# Master.net
KiCad netlist of a schematic drawn in EAGLE
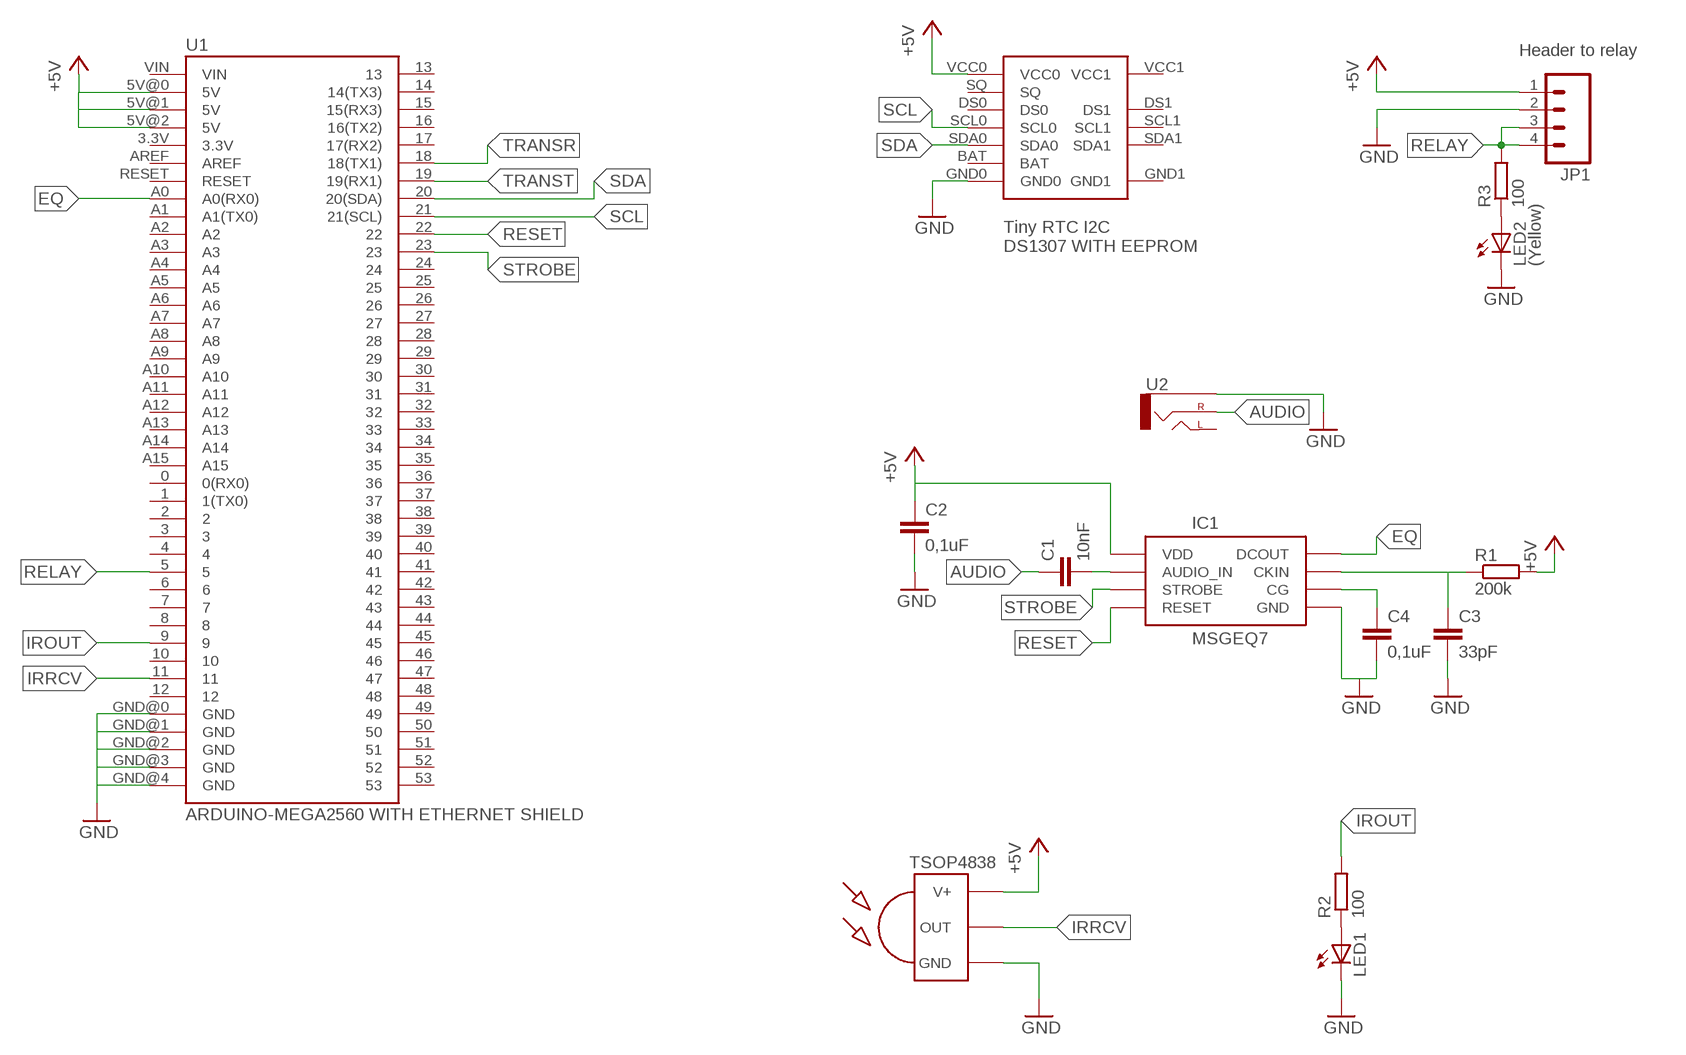
[diagram p0: schematic, sheet 1]

(export (version "E")
  (design (tool "Eeschema 10.0.6"))
  (components
    (comp (ref "C1")
      (value "10nF")
      (footprint "eagle-import:CAP-PTH-SMALLEZ")
      (libsource (lib "eagle-import") (part "CAPEZ"))
    )
    (comp (ref "C2")
      (value "0,1uF")
      (footprint "eagle-import:CAP-PTH-SMALLEZ")
      (libsource (lib "eagle-import") (part "CAPEZ"))
    )
    (comp (ref "C3")
      (value "33pF")
      (footprint "eagle-import:CAP-PTH-SMALLEZ")
      (libsource (lib "eagle-import") (part "CAPEZ"))
    )
    (comp (ref "C4")
      (value "0,1uF")
      (footprint "eagle-import:CAP-PTH-SMALLEZ")
      (libsource (lib "eagle-import") (part "CAPEZ"))
    )
    (comp (ref "IC1")
      (value "MSGEQ7DIP")
      (footprint "eagle-import:DIL08")
      (libsource (lib "eagle-import") (part "MSGEQ7DIP"))
    )
    (comp (ref "JP1")
      (value "M041.27MM")
      (footprint "eagle-import:1X04-1.27MM")
      (libsource (lib "eagle-import") (part "M041.27MM"))
    )
    (comp (ref "LED1")
      (value "LED5MM")
      (footprint "eagle-import:LED5MM")
      (libsource (lib "eagle-import") (part "LED5MM"))
    )
    (comp (ref "LED2")
      (value "(Yellow)")
      (footprint "eagle-import:LED3MM")
      (libsource (lib "eagle-import") (part "LED3MM"))
    )
    (comp (ref "R1")
      (value "200k")
      (footprint "eagle-import:0204_5")
      (libsource (lib "eagle-import") (part "R-EU_0204/5"))
    )
    (comp (ref "R2")
      (value "100")
      (footprint "eagle-import:0204_5")
      (libsource (lib "eagle-import") (part "R-EU_0204/5"))
    )
    (comp (ref "R3")
      (value "100")
      (footprint "eagle-import:0204_5")
      (libsource (lib "eagle-import") (part "R-EU_0204/5"))
    )
    (comp (ref "U$1")
      (value "TINYRTC")
      (footprint "eagle-import:TINYRTC")
      (libsource (lib "eagle-import") (part "TINYRTC"))
    )
    (comp (ref "U$2")
      (value "TSOP4838")
      (footprint "eagle-import:TSOP18XX")
      (libsource (lib "eagle-import") (part "TSOP4838"))
    )
    (comp (ref "U1")
      (value "ARDUINO-MEGA2560 WITH ETHERNET SHIELD")
      (footprint "eagle-import:ARDUINO_MEGA")
      (libsource (lib "eagle-import") (part "ARDUINO-MEGAFULL"))
    )
    (comp (ref "U2")
      (value "AUDIO-JACKPTH")
      (footprint "eagle-import:AUDIO-JACK")
      (libsource (lib "eagle-import") (part "AUDIO-JACKPTH"))
    )
  )
  (nets
    (net (code "1") (name "+5V") (class "Default")
      (node (ref "C2") (pin "1") (pinfunction "1_1") (pintype "passive"))
      (node (ref "IC1") (pin "1") (pinfunction "VDD_1") (pintype "input"))
      (node (ref "JP1") (pin "1") (pinfunction "1_1") (pintype "passive"))
      (node (ref "R1") (pin "2") (pinfunction "2_2") (pintype "passive"))
      (node (ref "U$1") (pin "VCC0") (pinfunction "VCC0_VCC0") (pintype "bidirectional"))
      (node (ref "U$2") (pin "VCC") (pinfunction "V+_VCC") (pintype "bidirectional"))
      (node (ref "U1") (pin "5V@0") (pinfunction "5V_5V@0") (pintype "bidirectional"))
      (node (ref "U1") (pin "5V@1") (pinfunction "5V_5V@1") (pintype "bidirectional"))
      (node (ref "U1") (pin "5V@2") (pinfunction "5V_5V@2") (pintype "bidirectional"))
    )
    (net (code "2") (name "AUDIO") (class "Default")
      (node (ref "C1") (pin "1") (pinfunction "1_1") (pintype "passive"))
      (node (ref "U2") (pin "RING") (pinfunction "RIGHT_RING") (pintype "bidirectional"))
    )
    (net (code "3") (name "EQ") (class "Default")
      (node (ref "IC1") (pin "3") (pinfunction "DCOUT_3") (pintype "bidirectional"))
      (node (ref "U1") (pin "A0") (pinfunction "A0(RX0)_A0") (pintype "bidirectional"))
    )
    (net (code "4") (name "GND") (class "Default")
      (node (ref "C2") (pin "2") (pinfunction "2_2") (pintype "passive"))
      (node (ref "C3") (pin "2") (pinfunction "2_2") (pintype "passive"))
      (node (ref "C4") (pin "2") (pinfunction "2_2") (pintype "passive"))
      (node (ref "IC1") (pin "2") (pinfunction "GND_2") (pintype "bidirectional"))
      (node (ref "JP1") (pin "2") (pinfunction "2_2") (pintype "passive"))
      (node (ref "LED1") (pin "K") (pinfunction "C_K") (pintype "passive"))
      (node (ref "LED2") (pin "K") (pinfunction "C_K") (pintype "passive"))
      (node (ref "U$1") (pin "GND0") (pinfunction "GND0_GND0") (pintype "bidirectional"))
      (node (ref "U$2") (pin "GND") (pinfunction "GND_GND") (pintype "bidirectional"))
      (node (ref "U1") (pin "GND@0") (pinfunction "GND_GND@0") (pintype "bidirectional"))
      (node (ref "U1") (pin "GND@1") (pinfunction "GND_GND@1") (pintype "bidirectional"))
      (node (ref "U1") (pin "GND@2") (pinfunction "GND_GND@2") (pintype "bidirectional"))
      (node (ref "U1") (pin "GND@3") (pinfunction "GND_GND@3") (pintype "bidirectional"))
      (node (ref "U1") (pin "GND@4") (pinfunction "GND_GND@4") (pintype "bidirectional"))
      (node (ref "U2") (pin "SLEEVE") (pinfunction "SLEEVE_SLEEVE") (pintype "bidirectional"))
    )
    (net (code "5") (name "IROUT") (class "Default")
      (node (ref "R2") (pin "2") (pinfunction "2_2") (pintype "passive"))
      (node (ref "U1") (pin "9") (pinfunction "9_9") (pintype "bidirectional"))
    )
    (net (code "6") (name "IRRCV") (class "Default")
      (node (ref "U$2") (pin "OUT") (pinfunction "OUT_OUT") (pintype "bidirectional"))
      (node (ref "U1") (pin "11") (pinfunction "11_11") (pintype "bidirectional"))
    )
    (net (code "7") (name "Net-(IC1-AUDIO_IN)") (class "Default")
      (node (ref "C1") (pin "2") (pinfunction "2_2") (pintype "passive"))
      (node (ref "IC1") (pin "5") (pinfunction "AUDIO_IN_5") (pintype "input"))
    )
    (net (code "8") (name "Net-(IC1-CG)") (class "Default")
      (node (ref "C4") (pin "1") (pinfunction "1_1") (pintype "passive"))
      (node (ref "IC1") (pin "6") (pinfunction "CG_6") (pintype "bidirectional"))
    )
    (net (code "9") (name "Net-(IC1-CKIN)") (class "Default")
      (node (ref "C3") (pin "1") (pinfunction "1_1") (pintype "passive"))
      (node (ref "IC1") (pin "8") (pinfunction "CKIN_8") (pintype "bidirectional"))
      (node (ref "R1") (pin "1") (pinfunction "1_1") (pintype "passive"))
    )
    (net (code "10") (name "Net-(LED1-PadA)") (class "Default")
      (node (ref "LED1") (pin "A") (pinfunction "A_A") (pintype "passive"))
      (node (ref "R2") (pin "1") (pinfunction "1_1") (pintype "passive"))
    )
    (net (code "11") (name "Net-(LED2-PadA)") (class "Default")
      (node (ref "LED2") (pin "A") (pinfunction "A_A") (pintype "passive"))
      (node (ref "R3") (pin "1") (pinfunction "1_1") (pintype "passive"))
    )
    (net (code "12") (name "RELAY") (class "Default")
      (node (ref "JP1") (pin "3") (pinfunction "3_3") (pintype "passive"))
      (node (ref "JP1") (pin "4") (pinfunction "4_4") (pintype "passive"))
      (node (ref "R3") (pin "2") (pinfunction "2_2") (pintype "passive"))
      (node (ref "U1") (pin "5") (pinfunction "5_5") (pintype "bidirectional"))
    )
    (net (code "13") (name "RESET") (class "Default")
      (node (ref "IC1") (pin "7") (pinfunction "RESET_7") (pintype "input"))
      (node (ref "U1") (pin "22") (pinfunction "22_22") (pintype "bidirectional"))
    )
    (net (code "14") (name "SCL") (class "Default")
      (node (ref "U$1") (pin "SCL0") (pinfunction "SCL0_SCL0") (pintype "bidirectional"))
      (node (ref "U1") (pin "21") (pinfunction "21(SCL)_21") (pintype "bidirectional"))
    )
    (net (code "15") (name "SDA") (class "Default")
      (node (ref "U$1") (pin "SDA0") (pinfunction "SDA0_SDA0") (pintype "bidirectional"))
      (node (ref "U1") (pin "20") (pinfunction "20(SDA)_20") (pintype "bidirectional"))
    )
    (net (code "16") (name "STROBE") (class "Default")
      (node (ref "IC1") (pin "4") (pinfunction "STROBE_4") (pintype "input"))
      (node (ref "U1") (pin "23") (pinfunction "23_23") (pintype "bidirectional"))
    )
    (net (code "17") (name "TRANSR") (class "Default")
      (node (ref "U1") (pin "18") (pinfunction "18(TX1)_18") (pintype "bidirectional"))
    )
    (net (code "18") (name "TRANST") (class "Default")
      (node (ref "U1") (pin "19") (pinfunction "19(RX1)_19") (pintype "bidirectional"))
    )
    (net (code "19") (name "unconnected-(U$1-PadBAT)") (class "Default")
      (node (ref "U$1") (pin "BAT") (pinfunction "BAT_BAT") (pintype "bidirectional"))
    )
    (net (code "20") (name "unconnected-(U$1-PadDS0)") (class "Default")
      (node (ref "U$1") (pin "DS0") (pinfunction "DS0_DS0") (pintype "bidirectional"))
    )
    (net (code "21") (name "unconnected-(U$1-PadDS1)") (class "Default")
      (node (ref "U$1") (pin "DS1") (pinfunction "DS1_DS1") (pintype "bidirectional"))
    )
    (net (code "22") (name "unconnected-(U$1-PadGND1)") (class "Default")
      (node (ref "U$1") (pin "GND1") (pinfunction "GND1_GND1") (pintype "bidirectional"))
    )
    (net (code "23") (name "unconnected-(U$1-PadSCL1)") (class "Default")
      (node (ref "U$1") (pin "SCL1") (pinfunction "SCL1_SCL1") (pintype "bidirectional"))
    )
    (net (code "24") (name "unconnected-(U$1-PadSDA1)") (class "Default")
      (node (ref "U$1") (pin "SDA1") (pinfunction "SDA1_SDA1") (pintype "bidirectional"))
    )
    (net (code "25") (name "unconnected-(U$1-PadSQ)") (class "Default")
      (node (ref "U$1") (pin "SQ") (pinfunction "SQ_SQ") (pintype "bidirectional"))
    )
    (net (code "26") (name "unconnected-(U$1-PadVCC1)") (class "Default")
      (node (ref "U$1") (pin "VCC1") (pinfunction "VCC1_VCC1") (pintype "bidirectional"))
    )
    (net (code "27") (name "unconnected-(U1-0(RX0)-Pad0)") (class "Default")
      (node (ref "U1") (pin "0") (pinfunction "0(RX0)_0") (pintype "bidirectional"))
    )
    (net (code "28") (name "unconnected-(U1-1(TX0)-Pad1)") (class "Default")
      (node (ref "U1") (pin "1") (pinfunction "1(TX0)_1") (pintype "bidirectional"))
    )
    (net (code "29") (name "unconnected-(U1-14(TX3)-Pad14)") (class "Default")
      (node (ref "U1") (pin "14") (pinfunction "14(TX3)_14") (pintype "bidirectional"))
    )
    (net (code "30") (name "unconnected-(U1-15(RX3)-Pad15)") (class "Default")
      (node (ref "U1") (pin "15") (pinfunction "15(RX3)_15") (pintype "bidirectional"))
    )
    (net (code "31") (name "unconnected-(U1-16(TX2)-Pad16)") (class "Default")
      (node (ref "U1") (pin "16") (pinfunction "16(TX2)_16") (pintype "bidirectional"))
    )
    (net (code "32") (name "unconnected-(U1-17(RX2)-Pad17)") (class "Default")
      (node (ref "U1") (pin "17") (pinfunction "17(RX2)_17") (pintype "bidirectional"))
    )
    (net (code "33") (name "unconnected-(U1-A1(TX0)-PadA1)") (class "Default")
      (node (ref "U1") (pin "A1") (pinfunction "A1(TX0)_A1") (pintype "bidirectional"))
    )
    (net (code "34") (name "unconnected-(U1-Pad2)") (class "Default")
      (node (ref "U1") (pin "2") (pinfunction "2_2") (pintype "bidirectional"))
    )
    (net (code "35") (name "unconnected-(U1-Pad3)") (class "Default")
      (node (ref "U1") (pin "3") (pinfunction "3_3") (pintype "bidirectional"))
    )
    (net (code "36") (name "unconnected-(U1-Pad3.3V)") (class "Default")
      (node (ref "U1") (pin "3.3V") (pinfunction "3.3V_3.3V") (pintype "bidirectional"))
    )
    (net (code "37") (name "unconnected-(U1-Pad4)") (class "Default")
      (node (ref "U1") (pin "4") (pinfunction "4_4") (pintype "bidirectional"))
    )
    (net (code "38") (name "unconnected-(U1-Pad6)") (class "Default")
      (node (ref "U1") (pin "6") (pinfunction "6_6") (pintype "bidirectional"))
    )
    (net (code "39") (name "unconnected-(U1-Pad7)") (class "Default")
      (node (ref "U1") (pin "7") (pinfunction "7_7") (pintype "bidirectional"))
    )
    (net (code "40") (name "unconnected-(U1-Pad8)") (class "Default")
      (node (ref "U1") (pin "8") (pinfunction "8_8") (pintype "bidirectional"))
    )
    (net (code "41") (name "unconnected-(U1-Pad10)") (class "Default")
      (node (ref "U1") (pin "10") (pinfunction "10_10") (pintype "bidirectional"))
    )
    (net (code "42") (name "unconnected-(U1-Pad12)") (class "Default")
      (node (ref "U1") (pin "12") (pinfunction "12_12") (pintype "bidirectional"))
    )
    (net (code "43") (name "unconnected-(U1-Pad13)") (class "Default")
      (node (ref "U1") (pin "13") (pinfunction "13_13") (pintype "bidirectional"))
    )
    (net (code "44") (name "unconnected-(U1-Pad24)") (class "Default")
      (node (ref "U1") (pin "24") (pinfunction "24_24") (pintype "bidirectional"))
    )
    (net (code "45") (name "unconnected-(U1-Pad25)") (class "Default")
      (node (ref "U1") (pin "25") (pinfunction "25_25") (pintype "bidirectional"))
    )
    (net (code "46") (name "unconnected-(U1-Pad26)") (class "Default")
      (node (ref "U1") (pin "26") (pinfunction "26_26") (pintype "bidirectional"))
    )
    (net (code "47") (name "unconnected-(U1-Pad27)") (class "Default")
      (node (ref "U1") (pin "27") (pinfunction "27_27") (pintype "bidirectional"))
    )
    (net (code "48") (name "unconnected-(U1-Pad28)") (class "Default")
      (node (ref "U1") (pin "28") (pinfunction "28_28") (pintype "bidirectional"))
    )
    (net (code "49") (name "unconnected-(U1-Pad29)") (class "Default")
      (node (ref "U1") (pin "29") (pinfunction "29_29") (pintype "bidirectional"))
    )
    (net (code "50") (name "unconnected-(U1-Pad30)") (class "Default")
      (node (ref "U1") (pin "30") (pinfunction "30_30") (pintype "bidirectional"))
    )
    (net (code "51") (name "unconnected-(U1-Pad31)") (class "Default")
      (node (ref "U1") (pin "31") (pinfunction "31_31") (pintype "bidirectional"))
    )
    (net (code "52") (name "unconnected-(U1-Pad32)") (class "Default")
      (node (ref "U1") (pin "32") (pinfunction "32_32") (pintype "bidirectional"))
    )
    (net (code "53") (name "unconnected-(U1-Pad33)") (class "Default")
      (node (ref "U1") (pin "33") (pinfunction "33_33") (pintype "bidirectional"))
    )
    (net (code "54") (name "unconnected-(U1-Pad34)") (class "Default")
      (node (ref "U1") (pin "34") (pinfunction "34_34") (pintype "bidirectional"))
    )
    (net (code "55") (name "unconnected-(U1-Pad35)") (class "Default")
      (node (ref "U1") (pin "35") (pinfunction "35_35") (pintype "bidirectional"))
    )
    (net (code "56") (name "unconnected-(U1-Pad36)") (class "Default")
      (node (ref "U1") (pin "36") (pinfunction "36_36") (pintype "bidirectional"))
    )
    (net (code "57") (name "unconnected-(U1-Pad37)") (class "Default")
      (node (ref "U1") (pin "37") (pinfunction "37_37") (pintype "bidirectional"))
    )
    (net (code "58") (name "unconnected-(U1-Pad38)") (class "Default")
      (node (ref "U1") (pin "38") (pinfunction "38_38") (pintype "bidirectional"))
    )
    (net (code "59") (name "unconnected-(U1-Pad39)") (class "Default")
      (node (ref "U1") (pin "39") (pinfunction "39_39") (pintype "bidirectional"))
    )
    (net (code "60") (name "unconnected-(U1-Pad40)") (class "Default")
      (node (ref "U1") (pin "40") (pinfunction "40_40") (pintype "bidirectional"))
    )
    (net (code "61") (name "unconnected-(U1-Pad41)") (class "Default")
      (node (ref "U1") (pin "41") (pinfunction "41_41") (pintype "bidirectional"))
    )
    (net (code "62") (name "unconnected-(U1-Pad42)") (class "Default")
      (node (ref "U1") (pin "42") (pinfunction "42_42") (pintype "bidirectional"))
    )
    (net (code "63") (name "unconnected-(U1-Pad43)") (class "Default")
      (node (ref "U1") (pin "43") (pinfunction "43_43") (pintype "bidirectional"))
    )
    (net (code "64") (name "unconnected-(U1-Pad44)") (class "Default")
      (node (ref "U1") (pin "44") (pinfunction "44_44") (pintype "bidirectional"))
    )
    (net (code "65") (name "unconnected-(U1-Pad45)") (class "Default")
      (node (ref "U1") (pin "45") (pinfunction "45_45") (pintype "bidirectional"))
    )
    (net (code "66") (name "unconnected-(U1-Pad46)") (class "Default")
      (node (ref "U1") (pin "46") (pinfunction "46_46") (pintype "bidirectional"))
    )
    (net (code "67") (name "unconnected-(U1-Pad47)") (class "Default")
      (node (ref "U1") (pin "47") (pinfunction "47_47") (pintype "bidirectional"))
    )
    (net (code "68") (name "unconnected-(U1-Pad48)") (class "Default")
      (node (ref "U1") (pin "48") (pinfunction "48_48") (pintype "bidirectional"))
    )
    (net (code "69") (name "unconnected-(U1-Pad49)") (class "Default")
      (node (ref "U1") (pin "49") (pinfunction "49_49") (pintype "bidirectional"))
    )
    (net (code "70") (name "unconnected-(U1-Pad50)") (class "Default")
      (node (ref "U1") (pin "50") (pinfunction "50_50") (pintype "bidirectional"))
    )
    (net (code "71") (name "unconnected-(U1-Pad51)") (class "Default")
      (node (ref "U1") (pin "51") (pinfunction "51_51") (pintype "bidirectional"))
    )
    (net (code "72") (name "unconnected-(U1-Pad52)") (class "Default")
      (node (ref "U1") (pin "52") (pinfunction "52_52") (pintype "bidirectional"))
    )
    (net (code "73") (name "unconnected-(U1-Pad53)") (class "Default")
      (node (ref "U1") (pin "53") (pinfunction "53_53") (pintype "bidirectional"))
    )
    (net (code "74") (name "unconnected-(U1-PadA2)") (class "Default")
      (node (ref "U1") (pin "A2") (pinfunction "A2_A2") (pintype "bidirectional"))
    )
    (net (code "75") (name "unconnected-(U1-PadA3)") (class "Default")
      (node (ref "U1") (pin "A3") (pinfunction "A3_A3") (pintype "bidirectional"))
    )
    (net (code "76") (name "unconnected-(U1-PadA4)") (class "Default")
      (node (ref "U1") (pin "A4") (pinfunction "A4_A4") (pintype "bidirectional"))
    )
    (net (code "77") (name "unconnected-(U1-PadA5)") (class "Default")
      (node (ref "U1") (pin "A5") (pinfunction "A5_A5") (pintype "bidirectional"))
    )
    (net (code "78") (name "unconnected-(U1-PadA6)") (class "Default")
      (node (ref "U1") (pin "A6") (pinfunction "A6_A6") (pintype "bidirectional"))
    )
    (net (code "79") (name "unconnected-(U1-PadA7)") (class "Default")
      (node (ref "U1") (pin "A7") (pinfunction "A7_A7") (pintype "bidirectional"))
    )
    (net (code "80") (name "unconnected-(U1-PadA8)") (class "Default")
      (node (ref "U1") (pin "A8") (pinfunction "A8_A8") (pintype "bidirectional"))
    )
    (net (code "81") (name "unconnected-(U1-PadA9)") (class "Default")
      (node (ref "U1") (pin "A9") (pinfunction "A9_A9") (pintype "bidirectional"))
    )
    (net (code "82") (name "unconnected-(U1-PadA10)") (class "Default")
      (node (ref "U1") (pin "A10") (pinfunction "A10_A10") (pintype "bidirectional"))
    )
    (net (code "83") (name "unconnected-(U1-PadA11)") (class "Default")
      (node (ref "U1") (pin "A11") (pinfunction "A11_A11") (pintype "bidirectional"))
    )
    (net (code "84") (name "unconnected-(U1-PadA12)") (class "Default")
      (node (ref "U1") (pin "A12") (pinfunction "A12_A12") (pintype "bidirectional"))
    )
    (net (code "85") (name "unconnected-(U1-PadA13)") (class "Default")
      (node (ref "U1") (pin "A13") (pinfunction "A13_A13") (pintype "bidirectional"))
    )
    (net (code "86") (name "unconnected-(U1-PadA14)") (class "Default")
      (node (ref "U1") (pin "A14") (pinfunction "A14_A14") (pintype "bidirectional"))
    )
    (net (code "87") (name "unconnected-(U1-PadA15)") (class "Default")
      (node (ref "U1") (pin "A15") (pinfunction "A15_A15") (pintype "bidirectional"))
    )
    (net (code "88") (name "unconnected-(U1-PadAREF)") (class "Default")
      (node (ref "U1") (pin "AREF") (pinfunction "AREF_AREF") (pintype "bidirectional"))
    )
    (net (code "89") (name "unconnected-(U1-PadRESET)") (class "Default")
      (node (ref "U1") (pin "RESET") (pinfunction "RESET_RESET") (pintype "bidirectional"))
    )
    (net (code "90") (name "unconnected-(U1-PadVIN)") (class "Default")
      (node (ref "U1") (pin "VIN") (pinfunction "VIN_VIN") (pintype "bidirectional"))
    )
    (net (code "91") (name "unconnected-(U2-LEFT-PadTIP)") (class "Default")
      (node (ref "U2") (pin "TIP") (pinfunction "LEFT_TIP") (pintype "bidirectional"))
    )
  )
)
